# 6v_BOOST.net
KiCad netlist of a schematic drawn in Altium Designer
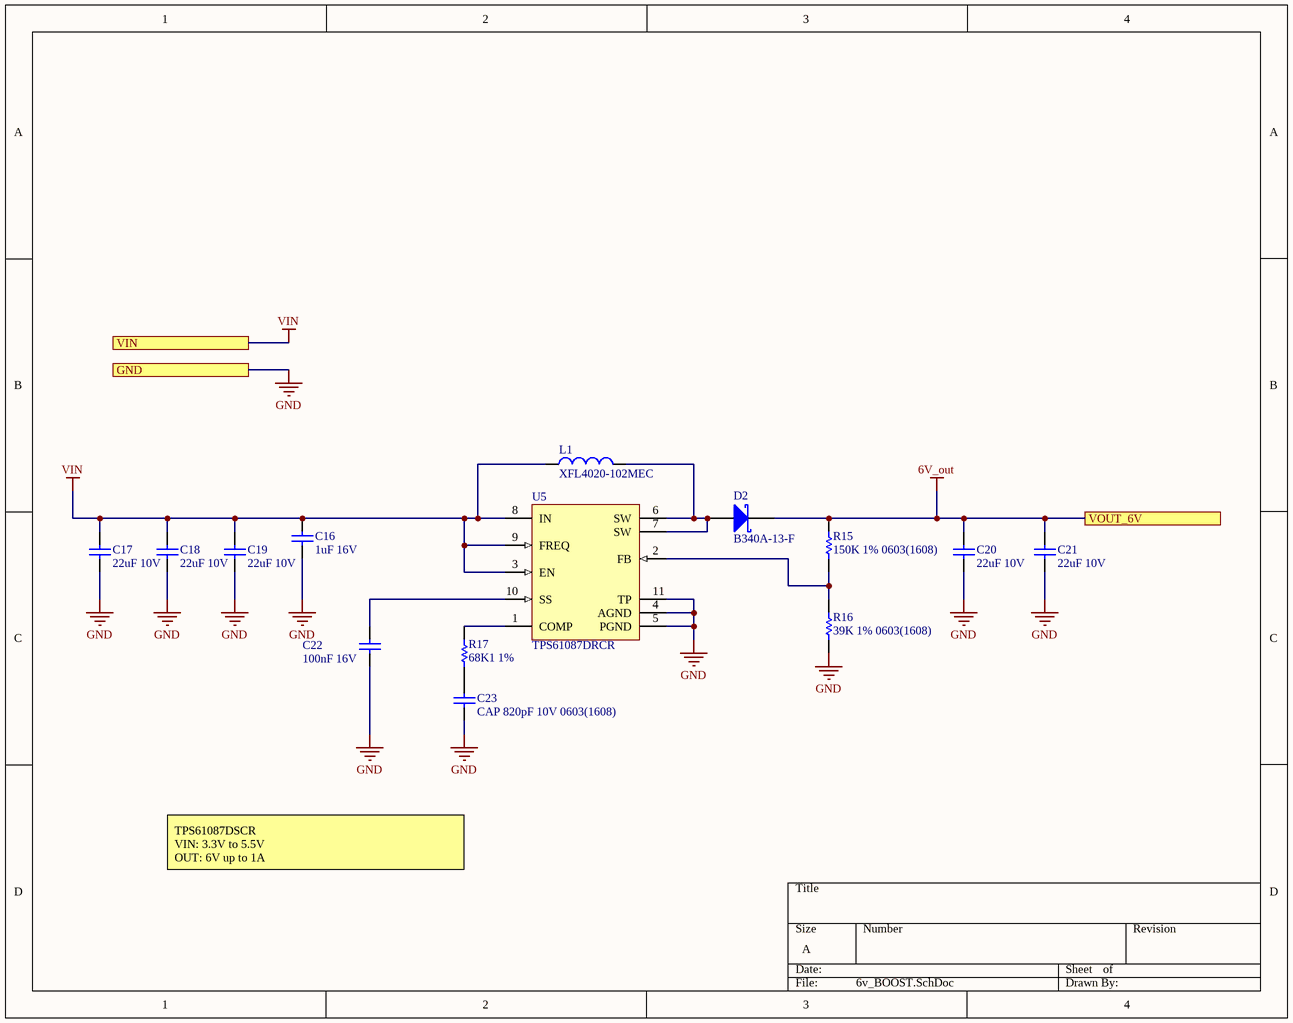
[diagram p0: 6v_BOOST.SchDoc]

(export (version "E")
  (design (tool "Eeschema 10.0.6"))
  (components
    (comp (ref "C16")
      (value "1uF 16V")
      (footprint "CAPC0603(1608)100_N")
      (description "CAP 1uF 16V ±5% 0603 (1608 Metric) Thickness 1mm SMD")
      (fields (field (name "TOLERANCE") "Â±5%"))
      (libsource (lib "Altium Content Vault") (part "CAP"))
    )
    (comp (ref "C17")
      (value "22uF 10V")
      (footprint "CAPC0805(2012)145_N")
      (description "CAP 22uF 10V ±20% 0805 (2012 Metric) Thickness 1.45mm SMD")
      (fields (field (name "TOLERANCE") "Â±20%"))
      (libsource (lib "Altium Content Vault") (part "CAP"))
    )
    (comp (ref "C18")
      (value "22uF 10V")
      (footprint "CAPC0805(2012)145_N")
      (description "CAP 22uF 10V ±20% 0805 (2012 Metric) Thickness 1.45mm SMD")
      (fields (field (name "TOLERANCE") "Â±20%"))
      (libsource (lib "Altium Content Vault") (part "CAP"))
    )
    (comp (ref "C19")
      (value "22uF 10V")
      (footprint "CAPC0805(2012)145_N")
      (description "CAP 22uF 10V ±20% 0805 (2012 Metric) Thickness 1.45mm SMD")
      (fields (field (name "TOLERANCE") "Â±20%"))
      (libsource (lib "Altium Content Vault") (part "CAP"))
    )
    (comp (ref "C20")
      (value "22uF 10V")
      (footprint "CAPC0805(2012)145_N")
      (description "CAP 22uF 10V ±20% 0805 (2012 Metric) Thickness 1.45mm SMD")
      (fields (field (name "TOLERANCE") "Â±20%"))
      (libsource (lib "Altium Content Vault") (part "CAP"))
    )
    (comp (ref "C21")
      (value "22uF 10V")
      (footprint "CAPC0805(2012)145_N")
      (description "CAP 22uF 10V ±20% 0805 (2012 Metric) Thickness 1.45mm SMD")
      (fields (field (name "TOLERANCE") "Â±20%"))
      (libsource (lib "Altium Content Vault") (part "CAP"))
    )
    (comp (ref "C22")
      (value "100nF 16V")
      (footprint "CAPC0603(1608)100_N")
      (description "CAP 100nF 16V ±10% 0603 (1608 Metric) Thickness 1mm SMD")
      (fields (field (name "TOLERANCE") "Â±10%"))
      (libsource (lib "Altium Content Vault") (part "CAP"))
    )
    (comp (ref "C23")
      (value "CAP 820pF 10V 0603(1608)")
      (footprint "CAPC0603(1608)100_N")
      (description "CAP 820pF 10V ±10% 0603 (1608 Metric) Thickness 1mm SMD")
      (fields (field (name "TOLERANCE") "Â±10%"))
      (libsource (lib "Altium Content Vault") (part "CAP"))
    )
    (comp (ref "D2")
      (value "B340A-13-F")
      (footprint "DIOD-SMA-2_V")
      (libsource (lib "Altium Content Vault") (part "DSKY-AK-2"))
    )
    (comp (ref "L1")
      (value "XFL4020-102MEC")
      (footprint "COIL-XFL4020_V")
      (description "Shielded Power Inductor, 1 uH, 64 MHz, -40 to 125 degC, 2-Pin SMD, RoHS, Tape and Reel")
      (fields (field (name "MANUFACTURER") "Coilcraft") (field (name "TOLERANCE") "20%"))
      (libsource (lib "Altium Content Vault") (part "IND-2"))
    )
    (comp (ref "R15")
      (value "150K 1% 0603(1608)")
      (footprint "RESC0603(1608)_N")
      (description "150K 0.1W 1% 0603 (1608 Metric)  SMD")
      (fields (field (name "TOLERANCE") "1 %") (field (name "POWER") "0.1 W"))
      (libsource (lib "Altium Content Vault") (part "RES"))
    )
    (comp (ref "R16")
      (value "39K 1% 0603(1608)")
      (footprint "RESC0603(1608)_N")
      (description "39K 0.1W 1% 0603 (1608 Metric)  SMD")
      (fields (field (name "TOLERANCE") "1 %") (field (name "POWER") "0.1 W"))
      (libsource (lib "Altium Content Vault") (part "RES"))
    )
    (comp (ref "R17")
      (value "68K1 1%")
      (footprint "RESC0603(1608)_N")
      (description "68K1 0.1W 1% 0603 (1608 Metric)  SMD")
      (fields (field (name "POWER") "0.1 W") (field (name "TOLERANCE") "1 %"))
      (libsource (lib "Altium Content Vault") (part "RES"))
    )
    (comp (ref "U5")
      (value "TPS61087DRCR")
      (footprint "DRC0010J_V")
      (fields (field (name "MANUFACTURER") "Texas Instruments"))
      (libsource (lib "Altium Content Vault") (part "TI-TPS61087DRC10-2400X1650TP"))
    )
  )
  (nets
    (net (code "1") (name "6V_out") (class "Default")
      (node (ref "C20") (pin "2") (pinfunction "2_2") (pintype "passive"))
      (node (ref "C21") (pin "2") (pinfunction "2_2") (pintype "passive"))
      (node (ref "D2") (pin "2") (pinfunction "K_2") (pintype "passive"))
      (node (ref "R15") (pin "2") (pinfunction "2_2") (pintype "passive"))
    )
    (net (code "2") (name "GND") (class "Default")
      (node (ref "C16") (pin "1") (pinfunction "1_1") (pintype "passive"))
      (node (ref "C17") (pin "1") (pinfunction "1_1") (pintype "passive"))
      (node (ref "C18") (pin "1") (pinfunction "1_1") (pintype "passive"))
      (node (ref "C19") (pin "1") (pinfunction "1_1") (pintype "passive"))
      (node (ref "C20") (pin "1") (pinfunction "1_1") (pintype "passive"))
      (node (ref "C21") (pin "1") (pinfunction "1_1") (pintype "passive"))
      (node (ref "C22") (pin "1") (pinfunction "1_1") (pintype "passive"))
      (node (ref "C23") (pin "1") (pinfunction "1_1") (pintype "passive"))
      (node (ref "R16") (pin "1") (pinfunction "1_1") (pintype "passive"))
      (node (ref "U5") (pin "11") (pinfunction "TP_11") (pintype "power_in"))
      (node (ref "U5") (pin "4") (pinfunction "AGND_4") (pintype "power_in"))
      (node (ref "U5") (pin "5") (pinfunction "PGND_5") (pintype "power_in"))
    )
    (net (code "3") (name "Net-(C23-Pad2)") (class "Default")
      (node (ref "C23") (pin "2") (pinfunction "2_2") (pintype "passive"))
      (node (ref "R17") (pin "1") (pinfunction "1_1") (pintype "passive"))
    )
    (net (code "4") (name "Net-(D2-A)") (class "Default")
      (node (ref "D2") (pin "1") (pinfunction "A_1") (pintype "passive"))
      (node (ref "L1") (pin "2") (pinfunction "2_2") (pintype "passive"))
      (node (ref "U5") (pin "6") (pinfunction "SW_6") (pintype "power_in"))
      (node (ref "U5") (pin "7") (pinfunction "SW_7") (pintype "power_in"))
    )
    (net (code "5") (name "Net-(U5-COMP)") (class "Default")
      (node (ref "R17") (pin "2") (pinfunction "2_2") (pintype "passive"))
      (node (ref "U5") (pin "1") (pinfunction "COMP_1") (pintype "passive"))
    )
    (net (code "6") (name "Net-(U5-FB)") (class "Default")
      (node (ref "R15") (pin "1") (pinfunction "1_1") (pintype "passive"))
      (node (ref "R16") (pin "2") (pinfunction "2_2") (pintype "passive"))
      (node (ref "U5") (pin "2") (pinfunction "FB_2") (pintype "input"))
    )
    (net (code "7") (name "Net-(U5-SS)") (class "Default")
      (node (ref "C22") (pin "2") (pinfunction "2_2") (pintype "passive"))
      (node (ref "U5") (pin "10") (pinfunction "SS_10") (pintype "input"))
    )
    (net (code "8") (name "VIN") (class "Default")
      (node (ref "C16") (pin "2") (pinfunction "2_2") (pintype "passive"))
      (node (ref "C17") (pin "2") (pinfunction "2_2") (pintype "passive"))
      (node (ref "C18") (pin "2") (pinfunction "2_2") (pintype "passive"))
      (node (ref "C19") (pin "2") (pinfunction "2_2") (pintype "passive"))
      (node (ref "L1") (pin "1") (pinfunction "1_1") (pintype "passive"))
      (node (ref "U5") (pin "3") (pinfunction "EN_3") (pintype "input"))
      (node (ref "U5") (pin "8") (pinfunction "IN_8") (pintype "power_in"))
      (node (ref "U5") (pin "9") (pinfunction "FREQ_9") (pintype "input"))
    )
  )
)
